# PIXRACER-IMU-R12.net
KiCad netlist of a schematic drawn in Altium Designer
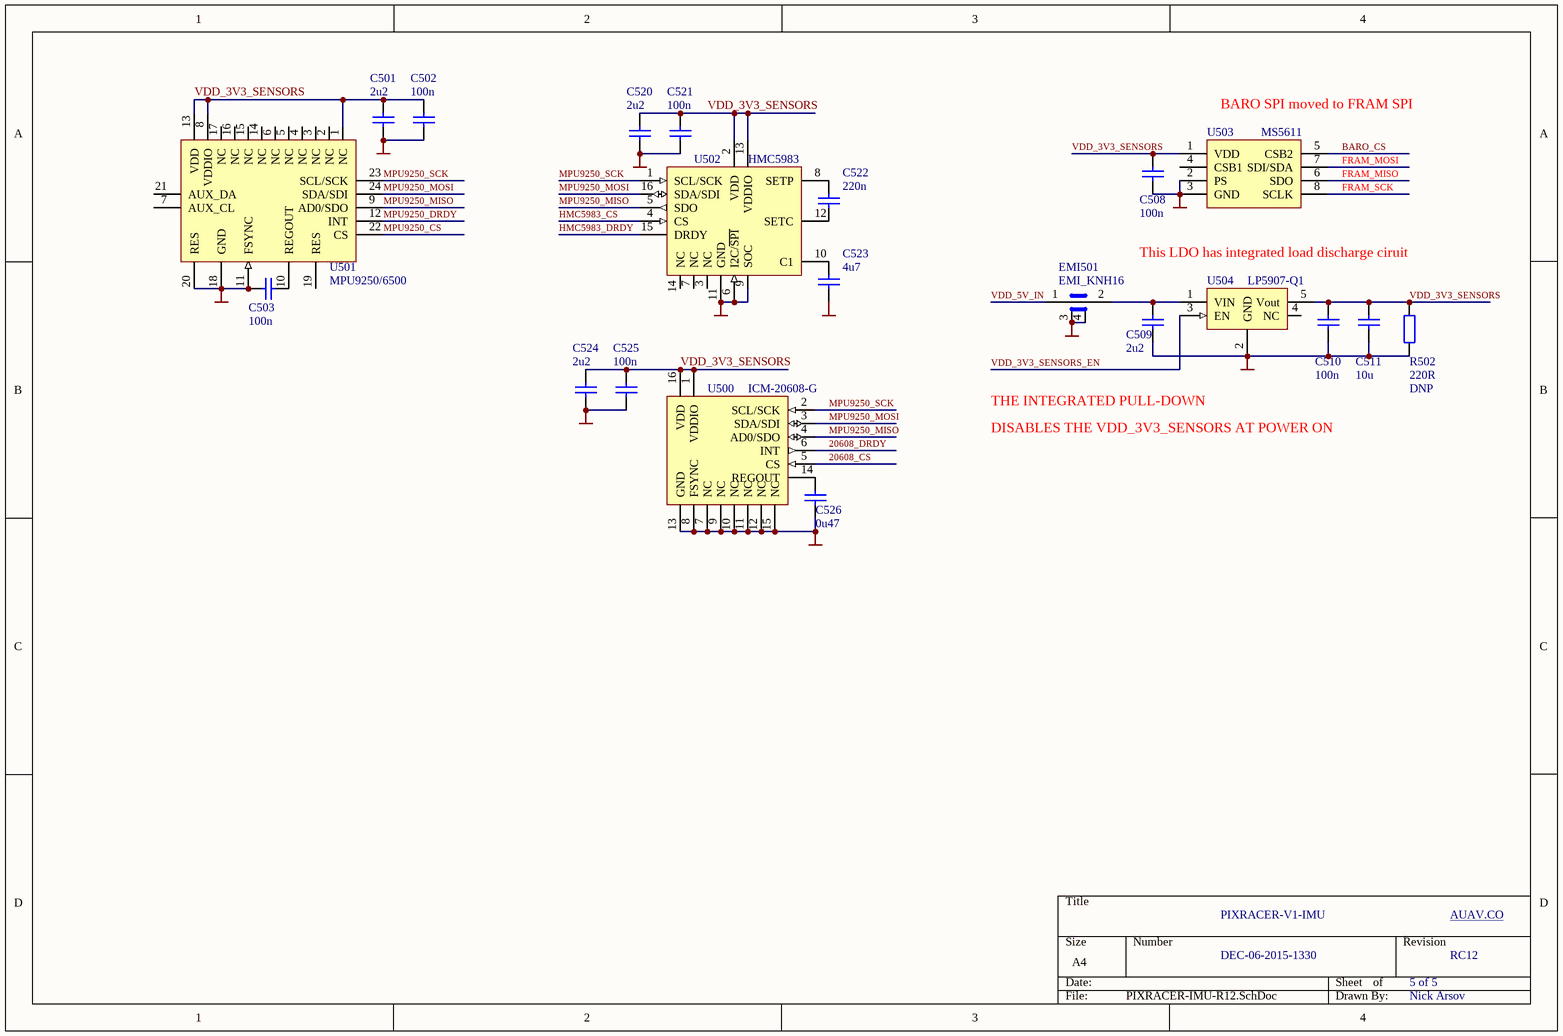
[diagram p0: PIXRACER-IMU-R12.SchDoc]

(export (version "E")
  (design (tool "Eeschema 10.0.6"))
  (components
    (comp (ref "C501")
      (value "2u2")
      (footprint "0402A")
      (description "Capacitor")
      (fields (field (name "PUBLISHER") "Altium Limited"))
      (libsource (lib "Miscellaneous Devices") (part "Cap"))
    )
    (comp (ref "C502")
      (value "100n")
      (footprint "0402A")
      (description "Capacitor")
      (fields (field (name "PUBLISHER") "Altium Limited"))
      (libsource (lib "Miscellaneous Devices") (part "Cap"))
    )
    (comp (ref "C503")
      (value "100n")
      (footprint "0402A")
      (description "Capacitor")
      (fields (field (name "PUBLISHER") "Altium Limited"))
      (libsource (lib "Miscellaneous Devices") (part "Cap"))
    )
    (comp (ref "C508")
      (value "100n")
      (footprint "0402A")
      (description "Capacitor")
      (fields (field (name "PUBLISHER") "Altium Limited"))
      (libsource (lib "Miscellaneous Devices") (part "Cap"))
    )
    (comp (ref "C509")
      (value "2u2")
      (footprint "0603A")
      (description "Capacitor")
      (fields (field (name "PUBLISHER") "Altium Limited"))
      (libsource (lib "Miscellaneous Devices") (part "Cap"))
    )
    (comp (ref "C510")
      (value "100n")
      (footprint "0603A")
      (description "Capacitor")
      (fields (field (name "PUBLISHER") "Altium Limited"))
      (libsource (lib "Miscellaneous Devices") (part "Cap"))
    )
    (comp (ref "C511")
      (value "10u")
      (footprint "0603A")
      (description "Capacitor")
      (fields (field (name "PUBLISHER") "Altium Limited"))
      (libsource (lib "Miscellaneous Devices") (part "Cap"))
    )
    (comp (ref "C520")
      (value "2u2")
      (footprint "0402A")
      (description "Capacitor")
      (fields (field (name "PUBLISHER") "Altium Limited"))
      (libsource (lib "Miscellaneous Devices") (part "Cap"))
    )
    (comp (ref "C521")
      (value "100n")
      (footprint "0402A")
      (description "Capacitor")
      (fields (field (name "PUBLISHER") "Altium Limited"))
      (libsource (lib "Miscellaneous Devices") (part "Cap"))
    )
    (comp (ref "C522")
      (value "220n")
      (footprint "0402A")
      (description "Capacitor")
      (fields (field (name "PUBLISHER") "Altium Limited"))
      (libsource (lib "Miscellaneous Devices") (part "Cap"))
    )
    (comp (ref "C523")
      (value "4u7")
      (footprint "0603A")
      (description "Capacitor")
      (fields (field (name "PUBLISHER") "Altium Limited"))
      (libsource (lib "Miscellaneous Devices") (part "Cap"))
    )
    (comp (ref "C524")
      (value "2u2")
      (footprint "0402A")
      (description "Capacitor")
      (fields (field (name "PUBLISHER") "Altium Limited"))
      (libsource (lib "Miscellaneous Devices") (part "Cap"))
    )
    (comp (ref "C525")
      (value "100n")
      (footprint "0402A")
      (description "Capacitor")
      (fields (field (name "PUBLISHER") "Altium Limited"))
      (libsource (lib "Miscellaneous Devices") (part "Cap"))
    )
    (comp (ref "C526")
      (value "0u47")
      (footprint "0402A")
      (description "Capacitor")
      (fields (field (name "PUBLISHER") "Altium Limited"))
      (libsource (lib "Miscellaneous Devices") (part "Cap"))
    )
    (comp (ref "EMI501")
      (value "EMI_KNH16")
      (footprint "EMI_KNH16_0603")
      (libsource (lib "My_Altium") (part "EMI_KNH16"))
    )
    (comp (ref "R502")
      (value "220R")
      (footprint "0402A")
      (description "Resistor")
      (fields (field (name "REM") "DNP") (field (name "PUBLISHER") "Altium Limited"))
      (libsource (lib "Miscellaneous Devices") (part "Res2"))
    )
    (comp (ref "U500")
      (value "ICM-20608-G")
      (footprint "HCLGA-16L")
      (libsource (lib "My_Altium") (part "ICM-20608-G"))
    )
    (comp (ref "U501")
      (value "MPU9250/6500")
      (footprint "MPU6500-9250")
      (libsource (lib "My_Altium") (part "MPU6500"))
    )
    (comp (ref "U502")
      (value "HMC5983")
      (footprint "HMC5883L")
      (libsource (lib "My_Altium") (part "HMC5983"))
    )
    (comp (ref "U503")
      (value "MS5611")
      (footprint "MS5611")
      (libsource (lib "My_Altium") (part "MS5611-01BA03"))
    )
    (comp (ref "U504")
      (value "LP5907-Q1")
      (footprint "SOT23-5")
      (libsource (lib "My_Altium") (part "LP5907-Q1"))
    )
  )
  (nets
    (net (code "1") (name "/20608_CS") (class "Default")
      (node (ref "U500") (pin "5") (pinfunction "CS_5") (pintype "input"))
    )
    (net (code "2") (name "/20608_DRDY") (class "Default")
      (node (ref "U500") (pin "6") (pinfunction "INT_6") (pintype "output"))
    )
    (net (code "3") (name "/BARO_CS") (class "Default")
      (node (ref "U503") (pin "5") (pinfunction "CSB2_5") (pintype "passive"))
    )
    (net (code "4") (name "/FRAM_MISO") (class "Default")
      (node (ref "U503") (pin "6") (pinfunction "SDO_6") (pintype "passive"))
    )
    (net (code "5") (name "/FRAM_MOSI") (class "Default")
      (node (ref "U503") (pin "7") (pinfunction "SDI/SDA_7") (pintype "passive"))
    )
    (net (code "6") (name "/FRAM_SCK") (class "Default")
      (node (ref "U503") (pin "8") (pinfunction "SCLK_8") (pintype "passive"))
    )
    (net (code "7") (name "/HMC5983_CS") (class "Default")
      (node (ref "U502") (pin "4") (pinfunction "CS_4") (pintype "input"))
    )
    (net (code "8") (name "/HMC5983_DRDY") (class "Default")
      (node (ref "U502") (pin "15") (pinfunction "DRDY_15") (pintype "passive"))
    )
    (net (code "9") (name "/MPU9250_CS") (class "Default")
      (node (ref "U501") (pin "22") (pinfunction "CS_22") (pintype "passive"))
    )
    (net (code "10") (name "/MPU9250_DRDY") (class "Default")
      (node (ref "U501") (pin "12") (pinfunction "INT_12") (pintype "passive"))
    )
    (net (code "11") (name "/MPU9250_MISO") (class "Default")
      (node (ref "U500") (pin "4") (pinfunction "AD0/SDO_4") (pintype "bidirectional"))
      (node (ref "U501") (pin "9") (pinfunction "AD0/SDO_9") (pintype "passive"))
      (node (ref "U502") (pin "5") (pinfunction "SDO_5") (pintype "output"))
    )
    (net (code "12") (name "/MPU9250_MOSI") (class "Default")
      (node (ref "U500") (pin "3") (pinfunction "SDA/SDI_3") (pintype "bidirectional"))
      (node (ref "U501") (pin "24") (pinfunction "SDA/SDI_24") (pintype "passive"))
      (node (ref "U502") (pin "16") (pinfunction "SDA/SDI_16") (pintype "bidirectional"))
    )
    (net (code "13") (name "/MPU9250_SCK") (class "Default")
      (node (ref "U500") (pin "2") (pinfunction "SCL/SCK_2") (pintype "input"))
      (node (ref "U501") (pin "23") (pinfunction "SCL/SCK_23") (pintype "passive"))
      (node (ref "U502") (pin "1") (pinfunction "SCL/SCK_1") (pintype "input"))
    )
    (net (code "14") (name "/VDD_3V3_SENSORS") (class "Default")
      (node (ref "C501") (pin "2") (pinfunction "2_2") (pintype "passive"))
      (node (ref "C502") (pin "2") (pinfunction "2_2") (pintype "passive"))
      (node (ref "C508") (pin "2") (pinfunction "2_2") (pintype "passive"))
      (node (ref "C510") (pin "2") (pinfunction "2_2") (pintype "passive"))
      (node (ref "C511") (pin "2") (pinfunction "2_2") (pintype "passive"))
      (node (ref "C520") (pin "2") (pinfunction "2_2") (pintype "passive"))
      (node (ref "C521") (pin "2") (pinfunction "2_2") (pintype "passive"))
      (node (ref "C524") (pin "2") (pinfunction "2_2") (pintype "passive"))
      (node (ref "C525") (pin "2") (pinfunction "2_2") (pintype "passive"))
      (node (ref "R502") (pin "2") (pinfunction "2_2") (pintype "passive"))
      (node (ref "U500") (pin "1") (pinfunction "VDDIO_1") (pintype "power_in"))
      (node (ref "U500") (pin "16") (pinfunction "VDD_16") (pintype "power_in"))
      (node (ref "U501") (pin "1") (pinfunction "NC_1") (pintype "passive"))
      (node (ref "U501") (pin "13") (pinfunction "VDD_13") (pintype "power_in"))
      (node (ref "U501") (pin "8") (pinfunction "VDDIO_8") (pintype "power_in"))
      (node (ref "U502") (pin "13") (pinfunction "VDDIO_13") (pintype "power_in"))
      (node (ref "U502") (pin "2") (pinfunction "VDD_2") (pintype "power_in"))
      (node (ref "U503") (pin "1") (pinfunction "VDD_1") (pintype "power_in"))
      (node (ref "U504") (pin "5") (pinfunction "Vout_5") (pintype "power_in"))
    )
    (net (code "15") (name "/VDD_3V3_SENSORS_EN") (class "Default")
      (node (ref "U504") (pin "3") (pinfunction "EN_3") (pintype "input"))
    )
    (net (code "16") (name "/VDD_5V_IN") (class "Default")
      (node (ref "EMI501") (pin "1") (pinfunction "L1_1") (pintype "passive"))
    )
    (net (code "17") (name "GND") (class "Default")
      (node (ref "C501") (pin "1") (pinfunction "1_1") (pintype "passive"))
      (node (ref "C502") (pin "1") (pinfunction "1_1") (pintype "passive"))
      (node (ref "C503") (pin "1") (pinfunction "1_1") (pintype "passive"))
      (node (ref "C508") (pin "1") (pinfunction "1_1") (pintype "passive"))
      (node (ref "C509") (pin "1") (pinfunction "1_1") (pintype "passive"))
      (node (ref "C510") (pin "1") (pinfunction "1_1") (pintype "passive"))
      (node (ref "C511") (pin "1") (pinfunction "1_1") (pintype "passive"))
      (node (ref "C520") (pin "1") (pinfunction "1_1") (pintype "passive"))
      (node (ref "C521") (pin "1") (pinfunction "1_1") (pintype "passive"))
      (node (ref "C523") (pin "1") (pinfunction "1_1") (pintype "passive"))
      (node (ref "C524") (pin "1") (pinfunction "1_1") (pintype "passive"))
      (node (ref "C525") (pin "1") (pinfunction "1_1") (pintype "passive"))
      (node (ref "C526") (pin "1") (pinfunction "1_1") (pintype "passive"))
      (node (ref "EMI501") (pin "3") (pinfunction "G_3") (pintype "power_in"))
      (node (ref "EMI501") (pin "4") (pinfunction "G_4") (pintype "passive"))
      (node (ref "R502") (pin "1") (pinfunction "1_1") (pintype "passive"))
      (node (ref "U500") (pin "10") (pinfunction "NC_10") (pintype "passive"))
      (node (ref "U500") (pin "11") (pinfunction "NC_11") (pintype "passive"))
      (node (ref "U500") (pin "12") (pinfunction "NC_12") (pintype "passive"))
      (node (ref "U500") (pin "13") (pinfunction "GND_13") (pintype "power_in"))
      (node (ref "U500") (pin "15") (pinfunction "NC_15") (pintype "passive"))
      (node (ref "U500") (pin "7") (pinfunction "NC_7") (pintype "passive"))
      (node (ref "U500") (pin "8") (pinfunction "FSYNC_8") (pintype "passive"))
      (node (ref "U500") (pin "9") (pinfunction "NC_9") (pintype "passive"))
      (node (ref "U501") (pin "11") (pinfunction "FSYNC_11") (pintype "input"))
      (node (ref "U501") (pin "18") (pinfunction "GND_18") (pintype "power_in"))
      (node (ref "U501") (pin "20") (pinfunction "RES_20") (pintype "passive"))
      (node (ref "U502") (pin "11") (pinfunction "GND_11") (pintype "power_in"))
      (node (ref "U502") (pin "6") (pinfunction "I2C/~{SPI}_6") (pintype "input"))
      (node (ref "U502") (pin "9") (pinfunction "SOC_9") (pintype "power_in"))
      (node (ref "U503") (pin "2") (pinfunction "PS_2") (pintype "passive"))
      (node (ref "U503") (pin "3") (pinfunction "GND_3") (pintype "power_in"))
      (node (ref "U504") (pin "2") (pinfunction "GND_2") (pintype "power_in"))
    )
    (net (code "18") (name "Net-(EMI501-L2)") (class "Default")
      (node (ref "C509") (pin "2") (pinfunction "2_2") (pintype "passive"))
      (node (ref "EMI501") (pin "2") (pinfunction "L2_2") (pintype "passive"))
      (node (ref "U504") (pin "1") (pinfunction "VIN_1") (pintype "power_in"))
    )
    (net (code "19") (name "Net-(U500-REGOUT)") (class "Default")
      (node (ref "C526") (pin "2") (pinfunction "2_2") (pintype "passive"))
      (node (ref "U500") (pin "14") (pinfunction "REGOUT_14") (pintype "passive"))
    )
    (net (code "20") (name "Net-(U501-REGOUT)") (class "Default")
      (node (ref "C503") (pin "2") (pinfunction "2_2") (pintype "passive"))
      (node (ref "U501") (pin "10") (pinfunction "REGOUT_10") (pintype "passive"))
    )
    (net (code "21") (name "Net-(U502-C1)") (class "Default")
      (node (ref "C523") (pin "2") (pinfunction "2_2") (pintype "passive"))
      (node (ref "U502") (pin "10") (pinfunction "C1_10") (pintype "passive"))
    )
    (net (code "22") (name "Net-(U502-SETC)") (class "Default")
      (node (ref "C522") (pin "1") (pinfunction "1_1") (pintype "passive"))
      (node (ref "U502") (pin "12") (pinfunction "SETC_12") (pintype "passive"))
    )
    (net (code "23") (name "Net-(U502-SETP)") (class "Default")
      (node (ref "C522") (pin "2") (pinfunction "2_2") (pintype "passive"))
      (node (ref "U502") (pin "8") (pinfunction "SETP_8") (pintype "passive"))
    )
    (net (code "24") (name "unconnected-(U501-AUX_CL-Pad7)") (class "Default")
      (node (ref "U501") (pin "7") (pinfunction "AUX_CL_7") (pintype "passive"))
    )
    (net (code "25") (name "unconnected-(U501-AUX_DA-Pad21)") (class "Default")
      (node (ref "U501") (pin "21") (pinfunction "AUX_DA_21") (pintype "passive"))
    )
    (net (code "26") (name "unconnected-(U501-NC-Pad2)") (class "Default")
      (node (ref "U501") (pin "2") (pinfunction "NC_2") (pintype "passive"))
    )
    (net (code "27") (name "unconnected-(U501-NC-Pad3)") (class "Default")
      (node (ref "U501") (pin "3") (pinfunction "NC_3") (pintype "passive"))
    )
    (net (code "28") (name "unconnected-(U501-NC-Pad4)") (class "Default")
      (node (ref "U501") (pin "4") (pinfunction "NC_4") (pintype "passive"))
    )
    (net (code "29") (name "unconnected-(U501-NC-Pad5)") (class "Default")
      (node (ref "U501") (pin "5") (pinfunction "NC_5") (pintype "passive"))
    )
    (net (code "30") (name "unconnected-(U501-NC-Pad6)") (class "Default")
      (node (ref "U501") (pin "6") (pinfunction "NC_6") (pintype "passive"))
    )
    (net (code "31") (name "unconnected-(U501-NC-Pad14)") (class "Default")
      (node (ref "U501") (pin "14") (pinfunction "NC_14") (pintype "passive"))
    )
    (net (code "32") (name "unconnected-(U501-NC-Pad15)") (class "Default")
      (node (ref "U501") (pin "15") (pinfunction "NC_15") (pintype "passive"))
    )
    (net (code "33") (name "unconnected-(U501-NC-Pad16)") (class "Default")
      (node (ref "U501") (pin "16") (pinfunction "NC_16") (pintype "passive"))
    )
    (net (code "34") (name "unconnected-(U501-NC-Pad17)") (class "Default")
      (node (ref "U501") (pin "17") (pinfunction "NC_17") (pintype "passive"))
    )
    (net (code "35") (name "unconnected-(U501-RES-Pad19)") (class "Default")
      (node (ref "U501") (pin "19") (pinfunction "RES_19") (pintype "passive"))
    )
    (net (code "36") (name "unconnected-(U502-NC-Pad3)") (class "Default")
      (node (ref "U502") (pin "3") (pinfunction "NC_3") (pintype "passive"))
    )
    (net (code "37") (name "unconnected-(U502-NC-Pad7)") (class "Default")
      (node (ref "U502") (pin "7") (pinfunction "NC_7") (pintype "passive"))
    )
    (net (code "38") (name "unconnected-(U502-NC-Pad14)") (class "Default")
      (node (ref "U502") (pin "14") (pinfunction "NC_14") (pintype "passive"))
    )
    (net (code "39") (name "unconnected-(U503-CSB1-Pad4)") (class "Default")
      (node (ref "U503") (pin "4") (pinfunction "CSB1_4") (pintype "passive"))
    )
    (net (code "40") (name "unconnected-(U504-NC-Pad4)") (class "Default")
      (node (ref "U504") (pin "4") (pinfunction "NC_4") (pintype "passive"))
    )
  )
)
